# bus_power.net
KiCad netlist of a schematic drawn in EAGLE
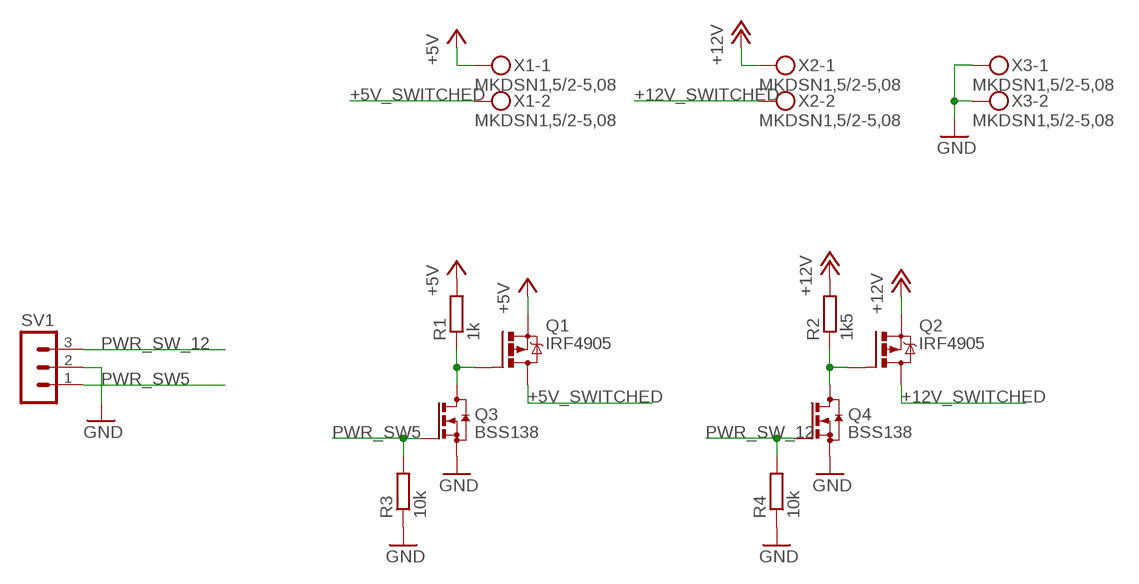
[diagram p0: schematic, sheet 1]

(export (version "E")
  (design (tool "Eeschema 10.0.6"))
  (components
    (comp (ref "Q1")
      (value "IRF4905")
      (footprint "eagle-import:TO220BV")
      (libsource (lib "eagle-import") (part "IRF9530"))
    )
    (comp (ref "Q2")
      (value "IRF4905")
      (footprint "eagle-import:TO220BV")
      (libsource (lib "eagle-import") (part "IRF9530"))
    )
    (comp (ref "Q3")
      (value "BSS138")
      (footprint "eagle-import:SOT23")
      (libsource (lib "eagle-import") (part "BSS123"))
    )
    (comp (ref "Q4")
      (value "BSS138")
      (footprint "eagle-import:SOT23")
      (libsource (lib "eagle-import") (part "BSS123"))
    )
    (comp (ref "R1")
      (value "1k")
      (footprint "eagle-import:R0805")
      (libsource (lib "eagle-import") (part "R-EU_R0805"))
    )
    (comp (ref "R2")
      (value "1k5")
      (footprint "eagle-import:R0805")
      (libsource (lib "eagle-import") (part "R-EU_R0805"))
    )
    (comp (ref "R3")
      (value "10k")
      (footprint "eagle-import:R0805")
      (libsource (lib "eagle-import") (part "R-EU_R0805"))
    )
    (comp (ref "R4")
      (value "10k")
      (footprint "eagle-import:R0805")
      (libsource (lib "eagle-import") (part "R-EU_R0805"))
    )
    (comp (ref "SV1")
      (value "MA03-1")
      (footprint "eagle-import:MA03-1")
      (libsource (lib "eagle-import") (part "MA03-1"))
    )
    (comp (ref "X1")
      (value "MKDSN1,5/2-5,08")
      (footprint "eagle-import:MKDSN1,5_2-5,08")
      (fields (field (name "MPN") "MKDSN 1,5/2-5.08"))
      (libsource (lib "eagle-import") (part "MKDSN1,5/2-5,08"))
    )
    (comp (ref "X2")
      (value "MKDSN1,5/2-5,08")
      (footprint "eagle-import:MKDSN1,5_2-5,08")
      (fields (field (name "MPN") "MKDSN 1,5/2-5.08"))
      (libsource (lib "eagle-import") (part "MKDSN1,5/2-5,08"))
    )
    (comp (ref "X3")
      (value "MKDSN1,5/2-5,08")
      (footprint "eagle-import:MKDSN1,5_2-5,08")
      (fields (field (name "MPN") "MKDSN 1,5/2-5.08"))
      (libsource (lib "eagle-import") (part "MKDSN1,5/2-5,08"))
    )
  )
  (nets
    (net (code "1") (name "+5V") (class "Default")
      (node (ref "Q1") (pin "S") (pinfunction "S_S") (pintype "passive"))
      (node (ref "R1") (pin "2") (pinfunction "2_2") (pintype "passive"))
      (node (ref "X1") (pin "1") (pinfunction "KL_1") (pintype "passive"))
    )
    (net (code "2") (name "+12V") (class "Default")
      (node (ref "Q2") (pin "S") (pinfunction "S_S") (pintype "passive"))
      (node (ref "R2") (pin "2") (pinfunction "2_2") (pintype "passive"))
      (node (ref "X2") (pin "1") (pinfunction "KL_1") (pintype "passive"))
    )
    (net (code "3") (name "/+5V_SWITCHED") (class "Default")
      (node (ref "Q1") (pin "D") (pinfunction "D_D") (pintype "passive"))
      (node (ref "X1") (pin "2") (pinfunction "KL_2") (pintype "passive"))
    )
    (net (code "4") (name "/+12V_SWITCHED") (class "Default")
      (node (ref "Q2") (pin "D") (pinfunction "D_D") (pintype "passive"))
      (node (ref "X2") (pin "2") (pinfunction "KL_2") (pintype "passive"))
    )
    (net (code "5") (name "/PWR_SW5") (class "Default")
      (node (ref "Q3") (pin "1") (pinfunction "G_1") (pintype "passive"))
      (node (ref "R3") (pin "2") (pinfunction "2_2") (pintype "passive"))
      (node (ref "SV1") (pin "1") (pinfunction "1_1") (pintype "passive"))
    )
    (net (code "6") (name "/PWR_SW_12") (class "Default")
      (node (ref "Q4") (pin "1") (pinfunction "G_1") (pintype "passive"))
      (node (ref "R4") (pin "2") (pinfunction "2_2") (pintype "passive"))
      (node (ref "SV1") (pin "3") (pinfunction "3_3") (pintype "passive"))
    )
    (net (code "7") (name "GND") (class "Default")
      (node (ref "Q3") (pin "2") (pinfunction "S_2") (pintype "passive"))
      (node (ref "Q4") (pin "2") (pinfunction "S_2") (pintype "passive"))
      (node (ref "R3") (pin "1") (pinfunction "1_1") (pintype "passive"))
      (node (ref "R4") (pin "1") (pinfunction "1_1") (pintype "passive"))
      (node (ref "SV1") (pin "2") (pinfunction "2_2") (pintype "passive"))
      (node (ref "X3") (pin "1") (pinfunction "KL_1") (pintype "passive"))
      (node (ref "X3") (pin "2") (pinfunction "KL_2") (pintype "passive"))
    )
    (net (code "8") (name "Net-(Q3-D)") (class "Default")
      (node (ref "Q1") (pin "G") (pinfunction "G_G") (pintype "passive"))
      (node (ref "Q3") (pin "3") (pinfunction "D_3") (pintype "passive"))
      (node (ref "R1") (pin "1") (pinfunction "1_1") (pintype "passive"))
    )
    (net (code "9") (name "Net-(Q4-D)") (class "Default")
      (node (ref "Q2") (pin "G") (pinfunction "G_G") (pintype "passive"))
      (node (ref "Q4") (pin "3") (pinfunction "D_3") (pintype "passive"))
      (node (ref "R2") (pin "1") (pinfunction "1_1") (pintype "passive"))
    )
  )
)
